# Charging_PCB.net
KiCad netlist of a schematic drawn in Altium Designer
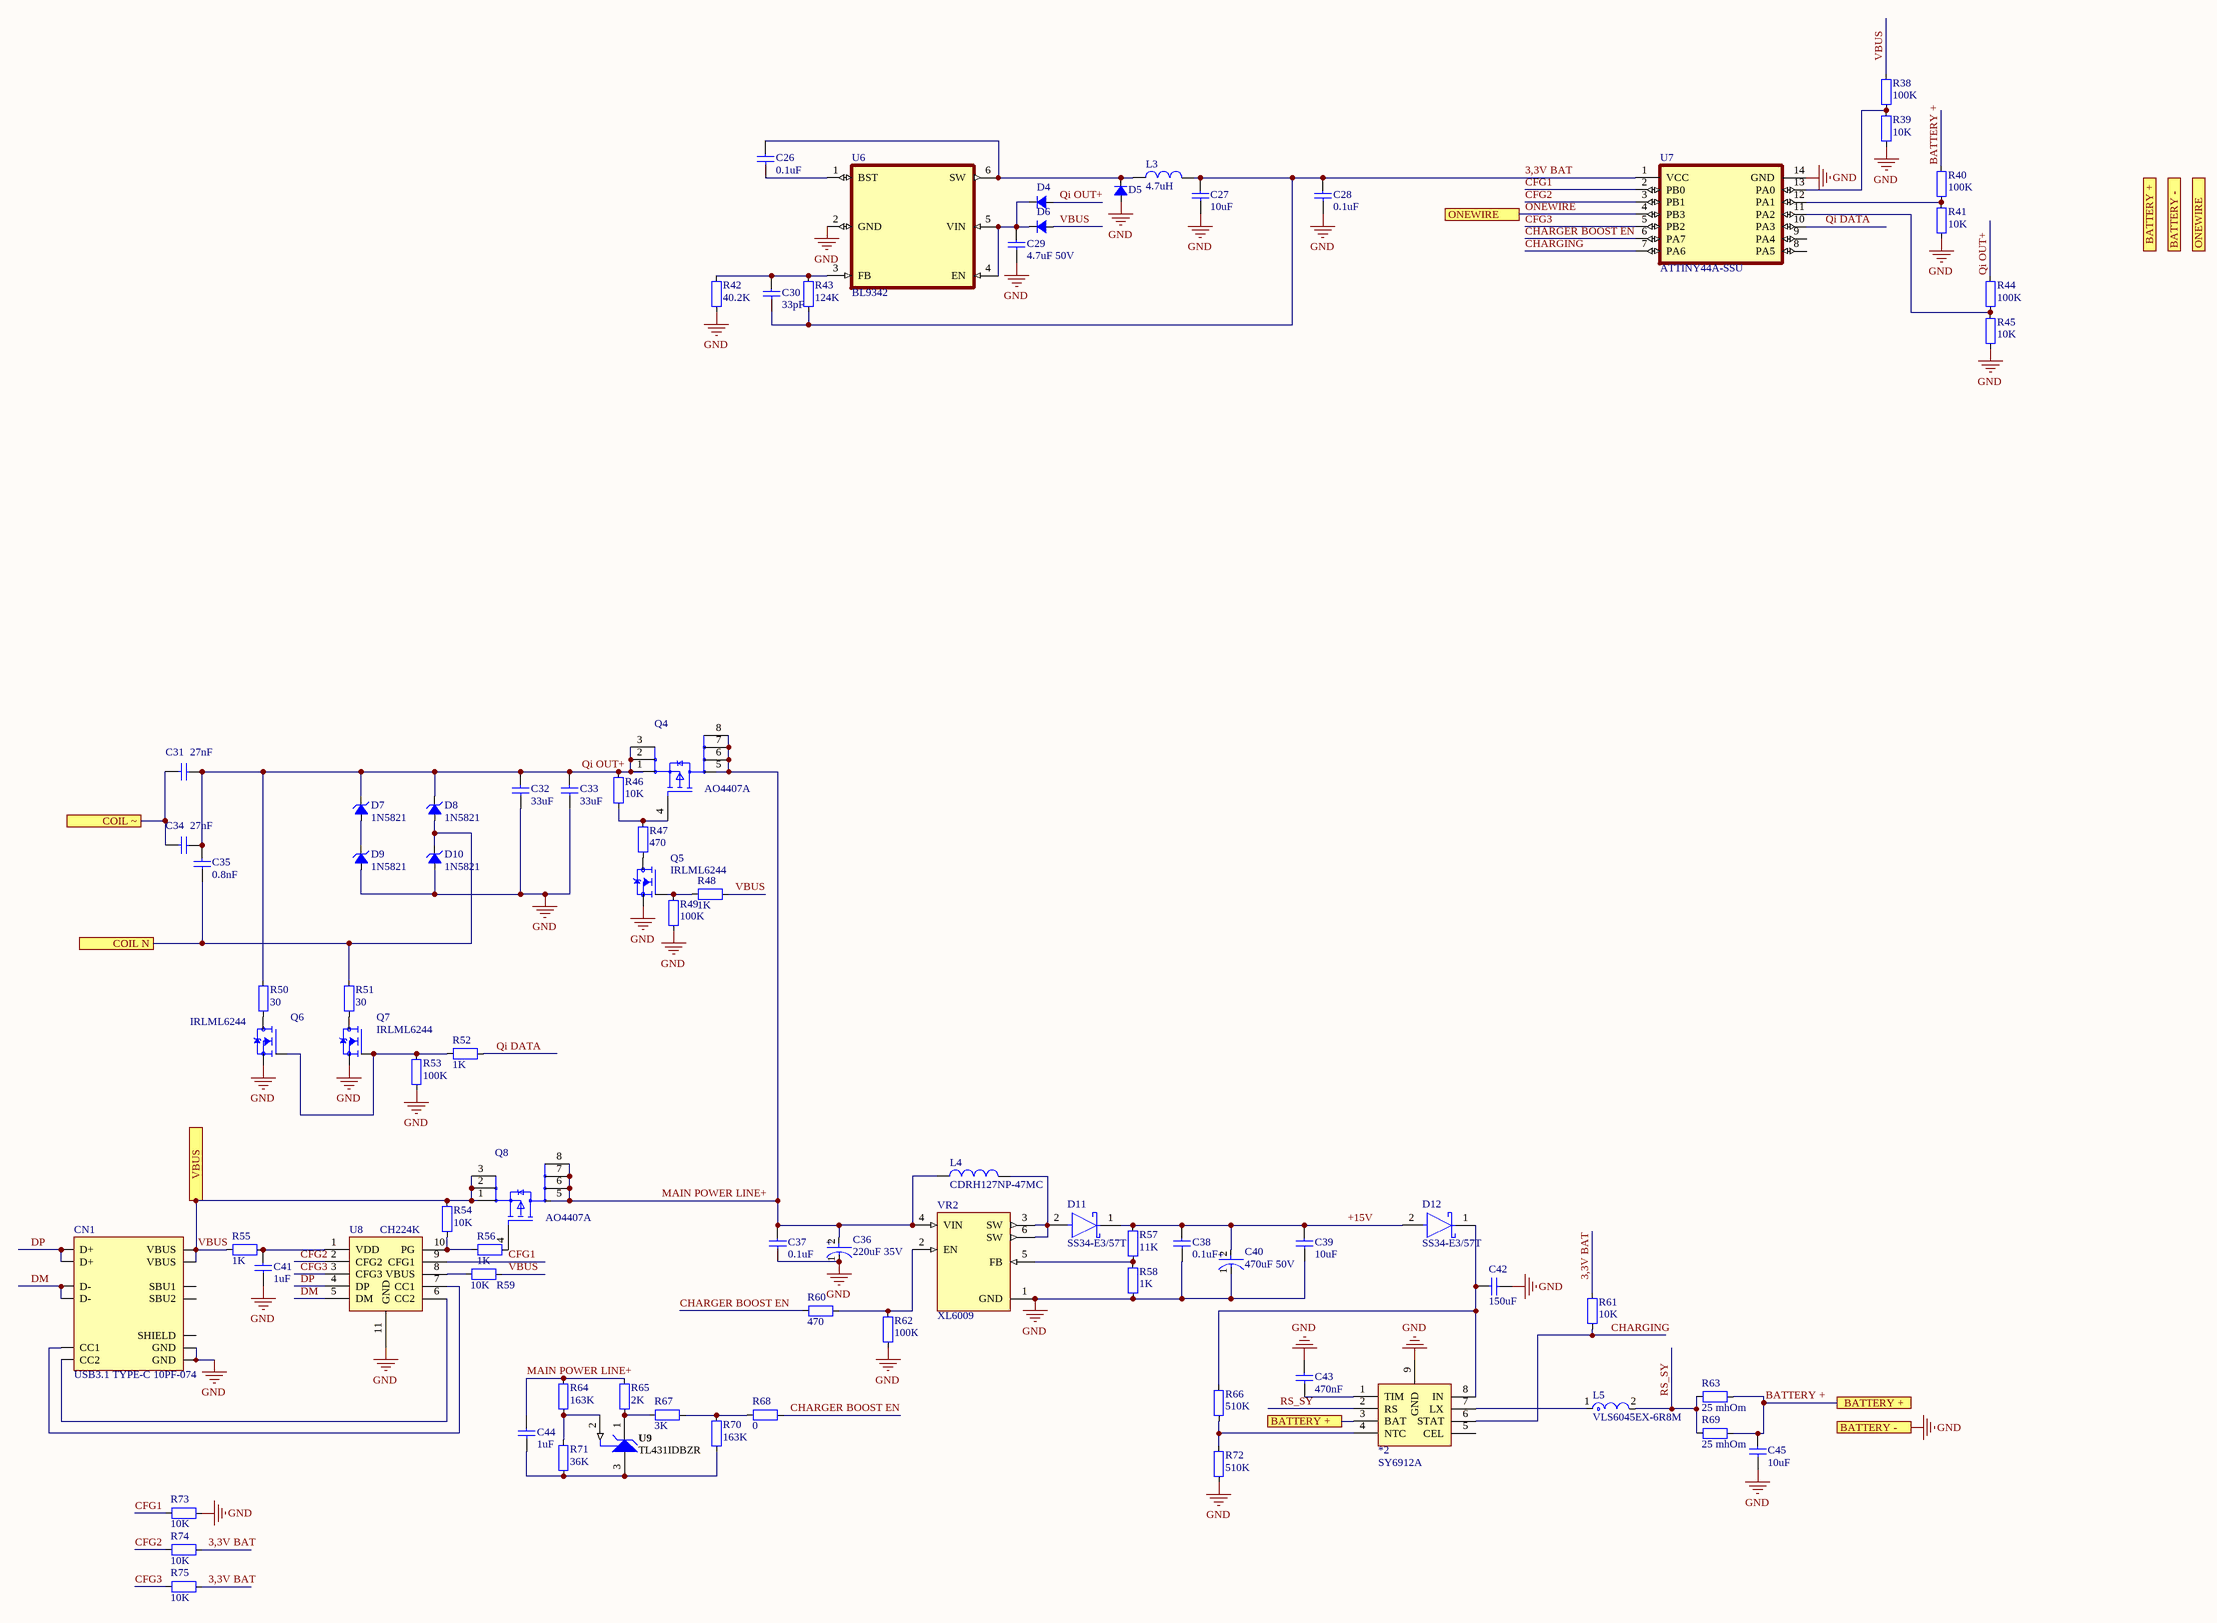
[diagram p0: Charging_PCB.SchDoc]

(export (version "E")
  (design (tool "Eeschema 10.0.6"))
  (components
    (comp (ref "*2") (value "SY6912A") (footprint "SO8") (libsource (lib "V_NB-IoT_3.1") (part "SY6912A")))
    (comp (ref "C26") (value "0.1uF") (footprint "C0805") (libsource (lib "V_NB-IoT_3.1") (part "CAP")))
    (comp (ref "C27") (value "10uF") (footprint "C0805") (libsource (lib "V_NB-IoT_3.1") (part "CAP")))
    (comp (ref "C28") (value "0.1uF") (footprint "C0805") (libsource (lib "V_NB-IoT_3.1") (part "CAP")))
    (comp (ref "C29") (value "4.7uF 50V") (footprint "C0805") (libsource (lib "V_NB-IoT_3.1") (part "CAP")))
    (comp (ref "C30") (value "33pF") (footprint "C0805") (libsource (lib "V_NB-IoT_3.1") (part "CAP")))
    (comp (ref "C31") (value "27nF") (footprint "1206") (libsource (lib "V_NB-IoT_3.1") (part "CAP")))
    (comp (ref "C32") (value "33uF") (footprint "1206") (libsource (lib "V_NB-IoT_3.1") (part "CAP")))
    (comp (ref "C33") (value "33uF") (footprint "1206") (libsource (lib "V_NB-IoT_3.1") (part "CAP")))
    (comp (ref "C34") (value "27nF") (footprint "1206") (libsource (lib "V_NB-IoT_3.1") (part "CAP")))
    (comp (ref "C35") (value "0.8nF") (footprint "1206") (libsource (lib "V_NB-IoT_3.1") (part "CAP")))
    (comp (ref "C36")
      (value "220uF 35V")
      (footprint "FP-RAD-TH-D_8_0_5-L_15_1-MFG")
      (description "Aluminum Electrolytic Capacitors (Radial Lead Type) 220uF ±20% 35V")
      (fields (field (name "TOLERANCE") "20%") (field (name "VOLTAGE") "35V"))
      (libsource (lib "V_NB-IoT_3.1") (part "CMP-05427-000678-1"))
    )
    (comp (ref "C37") (value "0.1uF") (footprint "1206") (libsource (lib "V_NB-IoT_3.1") (part "CAP")))
    (comp (ref "C38") (value "0.1uF") (footprint "1206") (libsource (lib "V_NB-IoT_3.1") (part "CAP")))
    (comp (ref "C39") (value "10uF") (footprint "CAPC1005X04L") (libsource (lib "V_NB-IoT_3.1") (part "CAP")))
    (comp (ref "C40")
      (value "470uF 50V")
      (footprint "FP-RAD-TH-D_10_0_5-L_20_2-MFG")
      (description "Aluminum Electrolytic Capacitors (Radial Lead Type) 10uF ±20% 400V")
      (fields (field (name "TOLERANCE") "20%") (field (name "VOLTAGE") "400V"))
      (libsource (lib "V_NB-IoT_3.1") (part "CAP 10x20"))
    )
    (comp (ref "C41") (value "1uF") (footprint "1206") (libsource (lib "V_NB-IoT_3.1") (part "CAP")))
    (comp (ref "C42")
      (value "150uF")
      (footprint "CAPC1005X04L")
      (libsource (lib "V_NB-IoT_3.1") (part "CAP"))
    )
    (comp (ref "C43") (value "470nF") (footprint "C0805") (libsource (lib "V_NB-IoT_3.1") (part "CAP")))
    (comp (ref "C44") (value "1uF") (footprint "1206") (libsource (lib "V_NB-IoT_3.1") (part "CAP")))
    (comp (ref "C45") (value "10uF") (footprint "CAPC1005X04L") (libsource (lib "V_NB-IoT_3.1") (part "CAP")))
    (comp (ref "CN1")
      (value "USB3.1 TYPE-C 10PF-074")
      (footprint "V_NB_IoT_3.1:USB3.1 TYPE-C 10PF-074")
      (description "XKB Connectivity USB-C Connector")
      (libsource (lib "V_NB-IoT_3.1") (part "USB3.1 TYPE-C 10PF-074"))
    )
    (comp (ref "D4")
      (value "~")
      (footprint "SOD-123")
      (description "Schottky diode SOD123")
      (libsource (lib "V_NB-IoT_3.1") (part "Diode_SOD123"))
    )
    (comp (ref "D5")
      (value "~")
      (footprint "SOD-123")
      (description "Schottky diode SOD123")
      (libsource (lib "V_NB-IoT_3.1") (part "Diode_SOD123"))
    )
    (comp (ref "D6")
      (value "~")
      (footprint "SOD-123")
      (description "Schottky diode SOD123")
      (libsource (lib "V_NB-IoT_3.1") (part "Diode_SOD123"))
    )
    (comp (ref "D7")
      (value "1N5821")
      (footprint "DO201-vertical")
      (description "DO201")
      (fields (field (name "MANUFACTURER PART NUMBER") "China"))
      (libsource (lib "V_NB-IoT_3.1") (part "Diode_Shottki_DO201V"))
    )
    (comp (ref "D8")
      (value "1N5821")
      (footprint "DO201-vertical")
      (description "DO201")
      (fields (field (name "MANUFACTURER PART NUMBER") "China"))
      (libsource (lib "V_NB-IoT_3.1") (part "Diode_Shottki_DO201V"))
    )
    (comp (ref "D9")
      (value "1N5821")
      (footprint "DO201-vertical")
      (description "DO201")
      (fields (field (name "MANUFACTURER PART NUMBER") "China"))
      (libsource (lib "V_NB-IoT_3.1") (part "Diode_Shottki_DO201V"))
    )
    (comp (ref "D10")
      (value "1N5821")
      (footprint "DO201-vertical")
      (description "DO201")
      (fields (field (name "MANUFACTURER PART NUMBER") "China"))
      (libsource (lib "V_NB-IoT_3.1") (part "Diode_Shottki_DO201V"))
    )
    (comp (ref "D11")
      (value "SS34-E3/57T")
      (footprint "FP-95402-MFG")
      (description "DIODE SCHOTTKY 40V 3A DO214AB")
      (fields
        (field (name "MANUFACTURER") "Vishay")
        (field (name "OCTOPART") "https://octopart.com/ss34-e3%2F57t-vishay-39552907")
      )
      (libsource (lib "V_NB-IoT_3.1") (part "SS34"))
    )
    (comp (ref "D12")
      (value "SS34-E3/57T")
      (footprint "FP-95402-MFG")
      (description "DIODE SCHOTTKY 40V 3A DO214AB")
      (fields
        (field (name "MANUFACTURER") "Vishay")
        (field (name "OCTOPART") "https://octopart.com/ss34-e3%2F57t-vishay-39552907")
      )
      (libsource (lib "V_NB-IoT_3.1") (part "SS34"))
    )
    (comp (ref "L3")
      (value "4.7uH")
      (footprint "CDRH3D16NP")
      (description "4,7µH Shielded Inductor 900mA 140mOhm Max Nonstandard")
      (fields
        (field (name "MANUFACTURER") "Sumida")
        (field (name "MANUFACTURER PART NUMBER") "CDRH3D16NP-100NC")
      )
      (libsource (lib "V_NB-IoT_3.1") (part "CDRH3D16NP"))
    )
    (comp (ref "L4")
      (value "CDRH127NP-47MC")
      (footprint "SUMI-CDRH127_V")
      (description "Power Inductor, 10 uH, +/- 20%, -40 to 100 degC, 2-Pin SMD, RoHS, Tape and Reel")
      (fields (field (name "MANUFACTURER") "Sumida") (field (name "TOLERANCE") "±20%"))
      (libsource (lib "V_NB-IoT_3.1") (part "CMP-2000-06084-1"))
    )
    (comp (ref "L5")
      (value "VLS6045EX-6R8M")
      (footprint "FP-VLS6045EX-100M-MFG")
      (description "FIXED IND  SMD")
      (fields (field (name "TOLERANCE") "20%"))
      (libsource (lib "V_NB-IoT_3.1") (part "VLS6045EX"))
    )
    (comp (ref "Q4")
      (value "AO4407A")
      (footprint "SOP-8_2-5R1S-IPC_B")
      (description "MOSFET P-CH 30V 9A 8SOP")
      (libsource (lib "V_NB-IoT_3.1") (part "MOSFET P-CH 30V 9A 8SOP"))
    )
    (comp (ref "Q5")
      (value "IRLML6244")
      (footprint "SOT-23")
      (description "MOSFET P-CH 30V 3.6A SOT-23-3")
      (fields
        (field (name "MF") "{'manufacturer': u'Infineon Technologies'}")
        (field (name "MP") "IRLML9301TRPBF")
      )
      (libsource (lib "V_NB-IoT_3.1") (part "IRLML6244"))
    )
    (comp (ref "Q6")
      (value "IRLML6244")
      (footprint "SOT-23")
      (description "MOSFET P-CH 30V 3.6A SOT-23-3")
      (fields
        (field (name "MF") "{'manufacturer': u'Infineon Technologies'}")
        (field (name "MP") "IRLML9301TRPBF")
      )
      (libsource (lib "V_NB-IoT_3.1") (part "IRLML6244"))
    )
    (comp (ref "Q7")
      (value "IRLML6244")
      (footprint "SOT-23")
      (description "MOSFET P-CH 30V 3.6A SOT-23-3")
      (fields
        (field (name "MF") "{'manufacturer': u'Infineon Technologies'}")
        (field (name "MP") "IRLML9301TRPBF")
      )
      (libsource (lib "V_NB-IoT_3.1") (part "IRLML6244"))
    )
    (comp (ref "Q8")
      (value "AO4407A")
      (footprint "SOP-8_2-5R1S-IPC_B")
      (description "MOSFET P-CH 30V 9A 8SOP")
      (libsource (lib "V_NB-IoT_3.1") (part "MOSFET P-CH 30V 9A 8SOP"))
    )
    (comp (ref "R38")
      (value "100K")
      (footprint "C0805")
      (description "Resistor SMD")
      (libsource (lib "V_NB-IoT_3.1") (part "RES SMD UNI"))
    )
    (comp (ref "R39")
      (value "10K")
      (footprint "C0805")
      (description "Resistor SMD")
      (libsource (lib "V_NB-IoT_3.1") (part "RES SMD UNI"))
    )
    (comp (ref "R40")
      (value "100K")
      (footprint "C0805")
      (description "Resistor SMD")
      (libsource (lib "V_NB-IoT_3.1") (part "RES SMD UNI"))
    )
    (comp (ref "R41")
      (value "10K")
      (footprint "C0805")
      (description "Resistor SMD")
      (libsource (lib "V_NB-IoT_3.1") (part "RES SMD UNI"))
    )
    (comp (ref "R42")
      (value "40.2K")
      (footprint "C0805")
      (description "Resistor SMD")
      (libsource (lib "V_NB-IoT_3.1") (part "RES SMD UNI"))
    )
    (comp (ref "R43")
      (value "124K")
      (footprint "C0805")
      (description "Resistor SMD")
      (libsource (lib "V_NB-IoT_3.1") (part "RES SMD UNI"))
    )
    (comp (ref "R44")
      (value "100K")
      (footprint "C0805")
      (description "Resistor SMD")
      (libsource (lib "V_NB-IoT_3.1") (part "RES SMD UNI"))
    )
    (comp (ref "R45")
      (value "10K")
      (footprint "C0805")
      (description "Resistor SMD")
      (libsource (lib "V_NB-IoT_3.1") (part "RES SMD UNI"))
    )
    (comp (ref "R46")
      (value "10K")
      (footprint "C0805")
      (description "Resistor SMD")
      (libsource (lib "V_NB-IoT_3.1") (part "RES SMD UNI"))
    )
    (comp (ref "R47")
      (value "470")
      (footprint "C0805")
      (description "Resistor SMD")
      (libsource (lib "V_NB-IoT_3.1") (part "RES SMD UNI"))
    )
    (comp (ref "R48")
      (value "1K")
      (footprint "C0805")
      (description "Resistor SMD")
      (libsource (lib "V_NB-IoT_3.1") (part "RES SMD UNI"))
    )
    (comp (ref "R49")
      (value "100K")
      (footprint "C0805")
      (description "Resistor SMD")
      (libsource (lib "V_NB-IoT_3.1") (part "RES SMD UNI"))
    )
    (comp (ref "R50")
      (value "30")
      (footprint "1206")
      (description "Resistor SMD")
      (libsource (lib "V_NB-IoT_3.1") (part "RES SMD UNI"))
    )
    (comp (ref "R51")
      (value "30")
      (footprint "1206")
      (description "Resistor SMD")
      (libsource (lib "V_NB-IoT_3.1") (part "RES SMD UNI"))
    )
    (comp (ref "R52")
      (value "1K")
      (footprint "C0805")
      (description "Resistor SMD")
      (libsource (lib "V_NB-IoT_3.1") (part "RES SMD UNI"))
    )
    (comp (ref "R53")
      (value "100K")
      (footprint "C0805")
      (description "Resistor SMD")
      (libsource (lib "V_NB-IoT_3.1") (part "RES SMD UNI"))
    )
    (comp (ref "R54")
      (value "10K")
      (footprint "C0805")
      (description "Resistor SMD")
      (libsource (lib "V_NB-IoT_3.1") (part "RES SMD UNI"))
    )
    (comp (ref "R55")
      (value "1K")
      (footprint "C0805")
      (description "Resistor SMD")
      (libsource (lib "V_NB-IoT_3.1") (part "RES SMD UNI"))
    )
    (comp (ref "R56")
      (value "1K")
      (footprint "C0805")
      (description "Resistor SMD")
      (libsource (lib "V_NB-IoT_3.1") (part "RES SMD UNI"))
    )
    (comp (ref "R57")
      (value "11K")
      (footprint "C0805")
      (description "Resistor SMD")
      (libsource (lib "V_NB-IoT_3.1") (part "RES SMD UNI"))
    )
    (comp (ref "R58")
      (value "1K")
      (footprint "C0805")
      (description "Resistor SMD")
      (libsource (lib "V_NB-IoT_3.1") (part "RES SMD UNI"))
    )
    (comp (ref "R59")
      (value "10K")
      (footprint "C0805")
      (description "Resistor SMD")
      (libsource (lib "V_NB-IoT_3.1") (part "RES SMD UNI"))
    )
    (comp (ref "R60")
      (value "470")
      (footprint "C0805")
      (description "Resistor SMD")
      (libsource (lib "V_NB-IoT_3.1") (part "RES SMD UNI"))
    )
    (comp (ref "R61")
      (value "10K")
      (footprint "C0805")
      (description "Resistor SMD")
      (libsource (lib "V_NB-IoT_3.1") (part "RES SMD UNI"))
    )
    (comp (ref "R62")
      (value "100К")
      (footprint "C0805")
      (description "Resistor SMD")
      (libsource (lib "V_NB-IoT_3.1") (part "RES SMD UNI"))
    )
    (comp (ref "R63")
      (value "25 mhOm")
      (footprint "1206")
      (description "Resistor SMD")
      (libsource (lib "V_NB-IoT_3.1") (part "RES SMD UNI"))
    )
    (comp (ref "R64")
      (value "163K")
      (footprint "C0805")
      (description "Resistor SMD")
      (libsource (lib "V_NB-IoT_3.1") (part "RES SMD UNI"))
    )
    (comp (ref "R65")
      (value "2K")
      (footprint "C0805")
      (description "Resistor SMD")
      (libsource (lib "V_NB-IoT_3.1") (part "RES SMD UNI"))
    )
    (comp (ref "R66")
      (value "510K")
      (footprint "C0805")
      (description "Resistor SMD")
      (libsource (lib "V_NB-IoT_3.1") (part "RES SMD UNI"))
    )
    (comp (ref "R67")
      (value "3K")
      (footprint "C0805")
      (description "Resistor SMD")
      (libsource (lib "V_NB-IoT_3.1") (part "RES SMD UNI"))
    )
    (comp (ref "R68")
      (value "0")
      (footprint "C0805")
      (description "Resistor SMD")
      (libsource (lib "V_NB-IoT_3.1") (part "RES SMD UNI"))
    )
    (comp (ref "R69")
      (value "25 mhOm")
      (footprint "1206")
      (description "Resistor SMD")
      (libsource (lib "V_NB-IoT_3.1") (part "RES SMD UNI"))
    )
    (comp (ref "R70")
      (value "163K")
      (footprint "C0805")
      (description "Resistor SMD")
      (libsource (lib "V_NB-IoT_3.1") (part "RES SMD UNI"))
    )
    (comp (ref "R71")
      (value "36K")
      (footprint "C0805")
      (description "Resistor SMD")
      (libsource (lib "V_NB-IoT_3.1") (part "RES SMD UNI"))
    )
    (comp (ref "R72")
      (value "510K")
      (footprint "C0805")
      (description "Resistor SMD")
      (libsource (lib "V_NB-IoT_3.1") (part "RES SMD UNI"))
    )
    (comp (ref "R73")
      (value "10K")
      (footprint "C0805")
      (description "Resistor SMD")
      (libsource (lib "V_NB-IoT_3.1") (part "RES SMD UNI"))
    )
    (comp (ref "R74")
      (value "10K")
      (footprint "C0805")
      (description "Resistor SMD")
      (libsource (lib "V_NB-IoT_3.1") (part "RES SMD UNI"))
    )
    (comp (ref "R75")
      (value "10K")
      (footprint "C0805")
      (description "Resistor SMD")
      (libsource (lib "V_NB-IoT_3.1") (part "RES SMD UNI"))
    )
    (comp (ref "U6")
      (value "BL9342")
      (footprint "V_NB_IoT_3.1:SOT50P160X60-6N")
      (fields (field (name "MF") "{'manufacturer': u'Texas Instruments'}"))
      (libsource (lib "V_NB-IoT_3.1") (part "BL9342"))
    )
    (comp (ref "U7")
      (value "ATTINY44A-SSU")
      (footprint "ATTINY44A-SSU:SOIC127P600X175-14N")
      (fields (field (name "MF") "{'manufacturer': u'Microchip'}"))
      (libsource (lib "V_NB-IoT_3.1") (part "ATTINY44A-SSU"))
    )
    (comp (ref "U8")
      (value "CH224K")
      (footprint "ESSOP10")
      (description "IC PD QC USB driver")
      (fields (field (name "MANUFACTURER") "ST") (field (name "MANUFACTURER PART NUMBER") "ST3485EBDR"))
      (libsource (lib "V_NB-IoT_3.1") (part "CH224K"))
    )
    (comp (ref "U9")
      (value "TL431IDBZR")
      (footprint "SOT95P237X112-3N")
      (fields (field (name "MANUFACTURER") "Texas Instruments"))
      (libsource (lib "V_NB-IoT_3.1") (part "TL431IDBZR"))
    )
    (comp (ref "VR2")
      (value "XL6009")
      (footprint "XL6009:DPAK170P1435X465-6N")
      (fields (field (name "MF") "{'manufacturer': u'XLSEMI'}"))
      (libsource (lib "V_NB-IoT_3.1") (part "XL6009"))
    )
  )
  (nets
    (net (code "1") (name "/+15V") (class "Default")
      (node (ref "C38") (pin "2") (pinfunction "2_2") (pintype "passive"))
      (node (ref "C39") (pin "2") (pinfunction "2_2") (pintype "passive"))
      (node (ref "C40") (pin "2") (pinfunction "A_2") (pintype "passive"))
      (node (ref "D11") (pin "1") (pinfunction "C_1") (pintype "passive"))
      (node (ref "D12") (pin "2") (pinfunction "A_2") (pintype "passive"))
      (node (ref "R57") (pin "1") (pinfunction "1_1") (pintype "passive"))
    )
    (net (code "2") (name "/3,3V BAT") (class "Default")
      (node (ref "C27") (pin "2") (pinfunction "2_2") (pintype "passive"))
      (node (ref "C28") (pin "2") (pinfunction "2_2") (pintype "passive"))
      (node (ref "C30") (pin "1") (pinfunction "1_1") (pintype "passive"))
      (node (ref "L3") (pin "2") (pinfunction "2_2") (pintype "passive"))
      (node (ref "R43") (pin "1") (pinfunction "1_1") (pintype "passive"))
      (node (ref "R61") (pin "2") (pinfunction "2_2") (pintype "passive"))
      (node (ref "R74") (pin "2") (pinfunction "2_2") (pintype "passive"))
      (node (ref "R75") (pin "2") (pinfunction "2_2") (pintype "passive"))
      (node (ref "U7") (pin "1") (pinfunction "VCC_1") (pintype "power_in"))
    )
    (net (code "3") (name "/BATTERY +") (class "Default")
      (node (ref "*2") (pin "3") (pinfunction "BAT_3") (pintype "passive"))
      (node (ref "C45") (pin "2") (pinfunction "2_2") (pintype "passive"))
      (node (ref "R40") (pin "2") (pinfunction "2_2") (pintype "passive"))
      (node (ref "R63") (pin "2") (pinfunction "2_2") (pintype "passive"))
      (node (ref "R69") (pin "2") (pinfunction "2_2") (pintype "passive"))
    )
    (net (code "4") (name "/CFG1") (class "Default")
      (node (ref "R73") (pin "1") (pinfunction "1_1") (pintype "passive"))
      (node (ref "U7") (pin "2") (pinfunction "PB0_2") (pintype "bidirectional"))
      (node (ref "U8") (pin "9") (pinfunction "CFG1_9") (pintype "power_in"))
    )
    (net (code "5") (name "/CFG2") (class "Default")
      (node (ref "R74") (pin "1") (pinfunction "1_1") (pintype "passive"))
      (node (ref "U7") (pin "3") (pinfunction "PB1_3") (pintype "bidirectional"))
      (node (ref "U8") (pin "2") (pinfunction "CFG2_2") (pintype "power_in"))
    )
    (net (code "6") (name "/CFG3") (class "Default")
      (node (ref "R75") (pin "1") (pinfunction "1_1") (pintype "passive"))
      (node (ref "U7") (pin "5") (pinfunction "PB2_5") (pintype "bidirectional"))
      (node (ref "U8") (pin "3") (pinfunction "CFG3_3") (pintype "power_in"))
    )
    (net (code "7") (name "/CHARGER BOOST EN") (class "Default")
      (node (ref "R60") (pin "2") (pinfunction "2_2") (pintype "passive"))
      (node (ref "R68") (pin "2") (pinfunction "2_2") (pintype "passive"))
      (node (ref "U7") (pin "6") (pinfunction "PA7_6") (pintype "bidirectional"))
    )
    (net (code "8") (name "/CHARGING") (class "Default")
      (node (ref "*2") (pin "6") (pinfunction "STAT_6") (pintype "passive"))
      (node (ref "R61") (pin "1") (pinfunction "1_1") (pintype "passive"))
      (node (ref "U7") (pin "7") (pinfunction "PA6_7") (pintype "bidirectional"))
    )
    (net (code "9") (name "/COIL N") (class "Default")
      (node (ref "C35") (pin "2") (pinfunction "2_2") (pintype "passive"))
      (node (ref "D10") (pin "2") (pinfunction "A_2") (pintype "passive"))
      (node (ref "D8") (pin "1") (pinfunction "K_1") (pintype "passive"))
      (node (ref "R51") (pin "2") (pinfunction "2_2") (pintype "passive"))
    )
    (net (code "10") (name "/COIL ~") (class "Default")
      (node (ref "C31") (pin "2") (pinfunction "2_2") (pintype "passive"))
      (node (ref "C34") (pin "2") (pinfunction "2_2") (pintype "passive"))
    )
    (net (code "11") (name "/DM") (class "Default")
      (node (ref "CN1") (pin "6") (pinfunction "D-_6") (pintype "passive"))
      (node (ref "CN1") (pin "9") (pinfunction "D-_9") (pintype "passive"))
      (node (ref "U8") (pin "5") (pinfunction "DM_5") (pintype "power_in"))
    )
    (net (code "12") (name "/DP") (class "Default")
      (node (ref "CN1") (pin "4") (pinfunction "D+_4") (pintype "passive"))
      (node (ref "CN1") (pin "7") (pinfunction "D+_7") (pintype "passive"))
      (node (ref "U8") (pin "4") (pinfunction "DP_4") (pintype "power_in"))
    )
    (net (code "13") (name "/MAIN POWER LINE+") (class "Default")
      (node (ref "C36") (pin "2") (pinfunction "A_2") (pintype "passive"))
      (node (ref "C37") (pin "2") (pinfunction "2_2") (pintype "passive"))
      (node (ref "C44") (pin "2") (pinfunction "2_2") (pintype "passive"))
      (node (ref "L4") (pin "1") (pinfunction "1_1") (pintype "passive"))
      (node (ref "Q4") (pin "5") (pinfunction "Drain_5") (pintype "passive"))
      (node (ref "Q4") (pin "6") (pinfunction "Drain_6") (pintype "passive"))
      (node (ref "Q4") (pin "7") (pinfunction "Drain_7") (pintype "passive"))
      (node (ref "Q4") (pin "8") (pinfunction "Drain_8") (pintype "passive"))
      (node (ref "Q8") (pin "5") (pinfunction "Drain_5") (pintype "passive"))
      (node (ref "Q8") (pin "6") (pinfunction "Drain_6") (pintype "passive"))
      (node (ref "Q8") (pin "7") (pinfunction "Drain_7") (pintype "passive"))
      (node (ref "Q8") (pin "8") (pinfunction "Drain_8") (pintype "passive"))
      (node (ref "R64") (pin "2") (pinfunction "2_2") (pintype "passive"))
      (node (ref "R65") (pin "2") (pinfunction "2_2") (pintype "passive"))
      (node (ref "VR2") (pin "4") (pinfunction "VIN_4") (pintype "input"))
    )
    (net (code "14") (name "/ONEWIRE") (class "Default")
      (node (ref "U7") (pin "4") (pinfunction "PB3_4") (pintype "bidirectional"))
    )
    (net (code "15") (name "/Qi DATA") (class "Default")
      (node (ref "R52") (pin "2") (pinfunction "2_2") (pintype "passive"))
      (node (ref "U7") (pin "10") (pinfunction "PA3_10") (pintype "bidirectional"))
    )
    (net (code "16") (name "/Qi OUT+") (class "Default")
      (node (ref "C31") (pin "1") (pinfunction "1_1") (pintype "passive"))
      (node (ref "C32") (pin "1") (pinfunction "1_1") (pintype "passive"))
      (node (ref "C33") (pin "1") (pinfunction "1_1") (pintype "passive"))
      (node (ref "C34") (pin "1") (pinfunction "1_1") (pintype "passive"))
      (node (ref "C35") (pin "1") (pinfunction "1_1") (pintype "passive"))
      (node (ref "D4") (pin "1") (pinfunction "A_1") (pintype "passive"))
      (node (ref "D7") (pin "2") (pinfunction "A_2") (pintype "passive"))
      (node (ref "D8") (pin "2") (pinfunction "A_2") (pintype "passive"))
      (node (ref "Q4") (pin "1") (pinfunction "Source_1") (pintype "passive"))
      (node (ref "Q4") (pin "2") (pinfunction "Source_2") (pintype "passive"))
      (node (ref "Q4") (pin "3") (pinfunction "Source_3") (pintype "passive"))
      (node (ref "R44") (pin "2") (pinfunction "2_2") (pintype "passive"))
      (node (ref "R46") (pin "2") (pinfunction "2_2") (pintype "passive"))
      (node (ref "R50") (pin "2") (pinfunction "2_2") (pintype "passive"))
    )
    (net (code "17") (name "/RS_SY") (class "Default")
      (node (ref "*2") (pin "2") (pinfunction "RS_2") (pintype "passive"))
      (node (ref "L5") (pin "2") (pinfunction "2_2") (pintype "passive"))
      (node (ref "R63") (pin "1") (pinfunction "1_1") (pintype "passive"))
      (node (ref "R69") (pin "1") (pinfunction "1_1") (pintype "passive"))
    )
    (net (code "18") (name "/VBUS") (class "Default")
      (node (ref "CN1") (pin "10") (pinfunction "VBUS_10") (pintype "power_in"))
      (node (ref "CN1") (pin "3") (pinfunction "VBUS_3") (pintype "power_in"))
      (node (ref "D6") (pin "1") (pinfunction "A_1") (pintype "passive"))
      (node (ref "Q8") (pin "1") (pinfunction "Source_1") (pintype "passive"))
      (node (ref "Q8") (pin "2") (pinfunction "Source_2") (pintype "passive"))
      (node (ref "Q8") (pin "3") (pinfunction "Source_3") (pintype "passive"))
      (node (ref "R38") (pin "2") (pinfunction "2_2") (pintype "passive"))
      (node (ref "R48") (pin "2") (pinfunction "2_2") (pintype "passive"))
      (node (ref "R54") (pin "2") (pinfunction "2_2") (pintype "passive"))
      (node (ref "R55") (pin "1") (pinfunction "1_1") (pintype "passive"))
      (node (ref "R59") (pin "2") (pinfunction "2_2") (pintype "passive"))
    )
    (net (code "19") (name "GND") (class "Default")
      (node (ref "*2") (pin "9") (pinfunction "GND_9") (pintype "passive"))
      (node (ref "C27") (pin "1") (pinfunction "1_1") (pintype "passive"))
      (node (ref "C28") (pin "1") (pinfunction "1_1") (pintype "passive"))
      (node (ref "C29") (pin "1") (pinfunction "1_1") (pintype "passive"))
      (node (ref "C32") (pin "2") (pinfunction "2_2") (pintype "passive"))
      (node (ref "C33") (pin "2") (pinfunction "2_2") (pintype "passive"))
      (node (ref "C36") (pin "1") (pinfunction "C_1") (pintype "passive"))
      (node (ref "C37") (pin "1") (pinfunction "1_1") (pintype "passive"))
      (node (ref "C38") (pin "1") (pinfunction "1_1") (pintype "passive"))
      (node (ref "C39") (pin "1") (pinfunction "1_1") (pintype "passive"))
      (node (ref "C40") (pin "1") (pinfunction "C_1") (pintype "passive"))
      (node (ref "C41") (pin "1") (pinfunction "1_1") (pintype "passive"))
      (node (ref "C42") (pin "2") (pinfunction "2_2") (pintype "passive"))
      (node (ref "C43") (pin "2") (pinfunction "2_2") (pintype "passive"))
      (node (ref "C45") (pin "1") (pinfunction "1_1") (pintype "passive"))
      (node (ref "CN1") (pin "1") (pinfunction "GND_1") (pintype "passive"))
      (node (ref "CN1") (pin "12") (pinfunction "GND_12") (pintype "power_in"))
      (node (ref "D10") (pin "1") (pinfunction "K_1") (pintype "passive"))
      (node (ref "D5") (pin "1") (pinfunction "A_1") (pintype "passive"))
      (node (ref "D9") (pin "1") (pinfunction "K_1") (pintype "passive"))
      (node (ref "Q5") (pin "2") (pinfunction "S_2") (pintype "passive"))
      (node (ref "Q6") (pin "2") (pinfunction "S_2") (pintype "passive"))
      (node (ref "Q7") (pin "2") (pinfunction "S_2") (pintype "passive"))
      (node (ref "R39") (pin "1") (pinfunction "1_1") (pintype "passive"))
      (node (ref "R41") (pin "1") (pinfunction "1_1") (pintype "passive"))
      (node (ref "R42") (pin "1") (pinfunction "1_1") (pintype "passive"))
      (node (ref "R45") (pin "1") (pinfunction "1_1") (pintype "passive"))
      (node (ref "R49") (pin "1") (pinfunction "1_1") (pintype "passive"))
      (node (ref "R53") (pin "1") (pinfunction "1_1") (pintype "passive"))
      (node (ref "R58") (pin "2") (pinfunction "2_2") (pintype "passive"))
      (node (ref "R62") (pin "2") (pinfunction "2_2") (pintype "passive"))
      (node (ref "R72") (pin "2") (pinfunction "2_2") (pintype "passive"))
      (node (ref "R73") (pin "2") (pinfunction "2_2") (pintype "passive"))
      (node (ref "U6") (pin "2") (pinfunction "GND_2") (pintype "bidirectional"))
      (node (ref "U7") (pin "14") (pinfunction "GND_14") (pintype "power_in"))
      (node (ref "U8") (pin "11") (pinfunction "GND_11") (pintype "passive"))
      (node (ref "VR2") (pin "1") (pinfunction "GND_1") (pintype "power_in"))
    )
    (net (code "20") (name "Net-(*2-IN)") (class "Default")
      (node (ref "*2") (pin "8") (pinfunction "IN_8") (pintype "passive"))
      (node (ref "C42") (pin "1") (pinfunction "1_1") (pintype "passive"))
      (node (ref "D12") (pin "1") (pinfunction "C_1") (pintype "passive"))
      (node (ref "R66") (pin "1") (pinfunction "1_1") (pintype "passive"))
    )
    (net (code "21") (name "Net-(*2-LX)") (class "Default")
      (node (ref "*2") (pin "7") (pinfunction "LX_7") (pintype "passive"))
      (node (ref "L5") (pin "1") (pinfunction "1_1") (pintype "passive"))
    )
    (net (code "22") (name "Net-(*2-NTC)") (class "Default")
      (node (ref "*2") (pin "4") (pinfunction "NTC_4") (pintype "passive"))
      (node (ref "R66") (pin "2") (pinfunction "2_2") (pintype "passive"))
      (node (ref "R72") (pin "1") (pinfunction "1_1") (pintype "passive"))
    )
    (net (code "23") (name "Net-(*2-TIM)") (class "Default")
      (node (ref "*2") (pin "1") (pinfunction "TIM_1") (pintype "passive"))
      (node (ref "C43") (pin "1") (pinfunction "1_1") (pintype "passive"))
    )
    (net (code "24") (name "Net-(CN1-CC1)") (class "Default")
      (node (ref "CN1") (pin "2") (pinfunction "CC1_2") (pintype "passive"))
      (node (ref "U8") (pin "7") (pinfunction "CC1_7") (pintype "power_in"))
    )
    (net (code "25") (name "Net-(CN1-CC2)") (class "Default")
      (node (ref "CN1") (pin "8") (pinfunction "CC2_8") (pintype "passive"))
      (node (ref "U8") (pin "6") (pinfunction "CC2_6") (pintype "power_in"))
    )
    (net (code "26") (name "Net-(D4-K)") (class "Default")
      (node (ref "C29") (pin "2") (pinfunction "2_2") (pintype "passive"))
      (node (ref "D4") (pin "2") (pinfunction "K_2") (pintype "passive"))
      (node (ref "D6") (pin "2") (pinfunction "K_2") (pintype "passive"))
      (node (ref "U6") (pin "4") (pinfunction "EN_4") (pintype "input"))
      (node (ref "U6") (pin "5") (pinfunction "VIN_5") (pintype "input"))
    )
    (net (code "27") (name "Net-(D5-K)") (class "Default")
      (node (ref "C26") (pin "2") (pinfunction "2_2") (pintype "passive"))
      (node (ref "D5") (pin "2") (pinfunction "K_2") (pintype "passive"))
      (node (ref "L3") (pin "1") (pinfunction "1_1") (pintype "passive"))
      (node (ref "U6") (pin "6") (pinfunction "SW_6") (pintype "output"))
    )
    (net (code "28") (name "Net-(D7-K)") (class "Default")
      (node (ref "D7") (pin "1") (pinfunction "K_1") (pintype "passive"))
      (node (ref "D9") (pin "2") (pinfunction "A_2") (pintype "passive"))
    )
    (net (code "29") (name "Net-(D11-A)") (class "Default")
      (node (ref "D11") (pin "2") (pinfunction "A_2") (pintype "passive"))
      (node (ref "L4") (pin "2") (pinfunction "2_2") (pintype "passive"))
      (node (ref "VR2") (pin "3") (pinfunction "SW_3") (pintype "output"))
      (node (ref "VR2") (pin "6") (pinfunction "SW_6") (pintype "output"))
    )
    (net (code "30") (name "Net-(Q4-Gate)") (class "Default")
      (node (ref "Q4") (pin "4") (pinfunction "Gate_4") (pintype "passive"))
      (node (ref "R46") (pin "1") (pinfunction "1_1") (pintype "passive"))
      (node (ref "R47") (pin "2") (pinfunction "2_2") (pintype "passive"))
    )
    (net (code "31") (name "Net-(Q5-D)") (class "Default")
      (node (ref "Q5") (pin "3") (pinfunction "D_3") (pintype "passive"))
      (node (ref "R47") (pin "1") (pinfunction "1_1") (pintype "passive"))
    )
    (net (code "32") (name "Net-(Q5-G)") (class "Default")
      (node (ref "Q5") (pin "1") (pinfunction "G_1") (pintype "passive"))
      (node (ref "R48") (pin "1") (pinfunction "1_1") (pintype "passive"))
      (node (ref "R49") (pin "2") (pinfunction "2_2") (pintype "passive"))
    )
    (net (code "33") (name "Net-(Q6-D)") (class "Default")
      (node (ref "Q6") (pin "3") (pinfunction "D_3") (pintype "passive"))
      (node (ref "R50") (pin "1") (pinfunction "1_1") (pintype "passive"))
    )
    (net (code "34") (name "Net-(Q6-G)") (class "Default")
      (node (ref "Q6") (pin "1") (pinfunction "G_1") (pintype "passive"))
      (node (ref "Q7") (pin "1") (pinfunction "G_1") (pintype "passive"))
      (node (ref "R52") (pin "1") (pinfunction "1_1") (pintype "passive"))
      (node (ref "R53") (pin "2") (pinfunction "2_2") (pintype "passive"))
    )
    (net (code "35") (name "Net-(Q7-D)") (class "Default")
      (node (ref "Q7") (pin "3") (pinfunction "D_3") (pintype "passive"))
      (node (ref "R51") (pin "1") (pinfunction "1_1") (pintype "passive"))
    )
    (net (code "36") (name "Net-(Q8-Gate)") (class "Default")
      (node (ref "Q8") (pin "4") (pinfunction "Gate_4") (pintype "passive"))
      (node (ref "R56") (pin "2") (pinfunction "2_2") (pintype "passive"))
    )
    (net (code "37") (name "Net-(R67-Pad2)") (class "Default")
      (node (ref "R67") (pin "2") (pinfunction "2_2") (pintype "passive"))
      (node (ref "R68") (pin "1") (pinfunction "1_1") (pintype "passive"))
      (node (ref "R70") (pin "2") (pinfunction "2_2") (pintype "passive"))
    )
    (net (code "38") (name "Net-(U6-BST)") (class "Default")
      (node (ref "C26") (pin "1") (pinfunction "1_1") (pintype "passive"))
      (node (ref "U6") (pin "1") (pinfunction "BST_1") (pintype "bidirectional"))
    )
    (net (code "39") (name "Net-(U6-FB)") (class "Default")
      (node (ref "C30") (pin "2") (pinfunction "2_2") (pintype "passive"))
      (node (ref "R42") (pin "2") (pinfunction "2_2") (pintype "passive"))
      (node (ref "R43") (pin "2") (pinfunction "2_2") (pintype "passive"))
      (node (ref "U6") (pin "3") (pinfunction "FB_3") (pintype "input"))
    )
    (net (code "40") (name "Net-(U7-PA0)") (class "Default")
      (node (ref "R38") (pin "1") (pinfunction "1_1") (pintype "passive"))
      (node (ref "R39") (pin "2") (pinfunction "2_2") (pintype "passive"))
      (node (ref "U7") (pin "13") (pinfunction "PA0_13") (pintype "bidirectional"))
    )
    (net (code "41") (name "Net-(U7-PA1)") (class "Default")
      (node (ref "R40") (pin "1") (pinfunction "1_1") (pintype "passive"))
      (node (ref "R41") (pin "2") (pinfunction "2_2") (pintype "passive"))
      (node (ref "U7") (pin "12") (pinfunction "PA1_12") (pintype "bidirectional"))
    )
    (net (code "42") (name "Net-(U7-PA2)") (class "Default")
      (node (ref "R44") (pin "1") (pinfunction "1_1") (pintype "passive"))
      (node (ref "R45") (pin "2") (pinfunction "2_2") (pintype "passive"))
      (node (ref "U7") (pin "11") (pinfunction "PA2_11") (pintype "bidirectional"))
    )
    (net (code "43") (name "Net-(U8-PG)") (class "Default")
      (node (ref "R54") (pin "1") (pinfunction "1_1") (pintype "passive"))
      (node (ref "R56") (pin "1") (pinfunction "1_1") (pintype "passive"))
      (node (ref "U8") (pin "10") (pinfunction "PG_10") (pintype "power_in"))
    )
    (net (code "44") (name "Net-(U8-VBUS)") (class "Default")
      (node (ref "R59") (pin "1") (pinfunction "1_1") (pintype "passive"))
      (node (ref "U8") (pin "8") (pinfunction "VBUS_8") (pintype "power_in"))
    )
    (net (code "45") (name "Net-(U8-VDD)") (class "Default")
      (node (ref "C41") (pin "2") (pinfunction "2_2") (pintype "passive"))
      (node (ref "R55") (pin "2") (pinfunction "2_2") (pintype "passive"))
      (node (ref "U8") (pin "1") (pinfunction "VDD_1") (pintype "power_in"))
    )
    (net (code "46") (name "Net-(U9-ANODE)") (class "Default")
      (node (ref "C44") (pin "1") (pinfunction "1_1") (pintype "passive"))
      (node (ref "R70") (pin "1") (pinfunction "1_1") (pintype "passive"))
      (node (ref "R71") (pin "1") (pinfunction "1_1") (pintype "passive"))
      (node (ref "U9") (pin "3") (pinfunction "ANODE_3") (pintype "passive"))
    )
    (net (code "47") (name "Net-(U9-CATHODE)") (class "Default")
      (node (ref "R65") (pin "1") (pinfunction "1_1") (pintype "passive"))
      (node (ref "R67") (pin "1") (pinfunction "1_1") (pintype "passive"))
      (node (ref "U9") (pin "1") (pinfunction "CATHODE_1") (pintype "passive"))
    )
    (net (code "48") (name "Net-(U9-REF)") (class "Default")
      (node (ref "R64") (pin "1") (pinfunction "1_1") (pintype "passive"))
      (node (ref "R71") (pin "2") (pinfunction "2_2") (pintype "passive"))
      (node (ref "U9") (pin "2") (pinfunction "REF_2") (pintype "input"))
    )
    (net (code "49") (name "Net-(VR2-EN)") (class "Default")
      (node (ref "R60") (pin "1") (pinfunction "1_1") (pintype "passive"))
      (node (ref "R62") (pin "1") (pinfunction "1_1") (pintype "passive"))
      (node (ref "VR2") (pin "2") (pinfunction "EN_2") (pintype "input"))
    )
    (net (code "50") (name "Net-(VR2-FB)") (class "Default")
      (node (ref "R57") (pin "2") (pinfunction "2_2") (pintype "passive"))
      (node (ref "R58") (pin "1") (pinfunction "1_1") (pintype "passive"))
      (node (ref "VR2") (pin "5") (pinfunction "FB_5") (pintype "input"))
    )
    (net (code "51") (name "unconnected-(*2-CEL-Pad5)") (class "Default")
      (node (ref "*2") (pin "5") (pinfunction "CEL_5") (pintype "passive"))
    )
    (net (code "52") (name "unconnected-(CN1-SBU1-Pad11)") (class "Default")
      (node (ref "CN1") (pin "11") (pinfunction "SBU1_11") (pintype "passive"))
    )
    (net (code "53") (name "unconnected-(CN1-SBU2-Pad5)") (class "Default")
      (node (ref "CN1") (pin "5") (pinfunction "SBU2_5") (pintype "passive"))
    )
    (net (code "54") (name "unconnected-(CN1-SHIELD-PadMH)") (class "Default")
      (node (ref "CN1") (pin "MH") (pinfunction "SHIELD_MH") (pintype "passive"))
    )
    (net (code "55") (name "unconnected-(U7-PA4-Pad9)") (class "Default")
      (node (ref "U7") (pin "9") (pinfunction "PA4_9") (pintype "bidirectional"))
    )
    (net (code "56") (name "unconnected-(U7-PA5-Pad8)") (class "Default")
      (node (ref "U7") (pin "8") (pinfunction "PA5_8") (pintype "bidirectional"))
    )
  )
)
